# Arduino.net
KiCad netlist of a schematic drawn in EAGLE
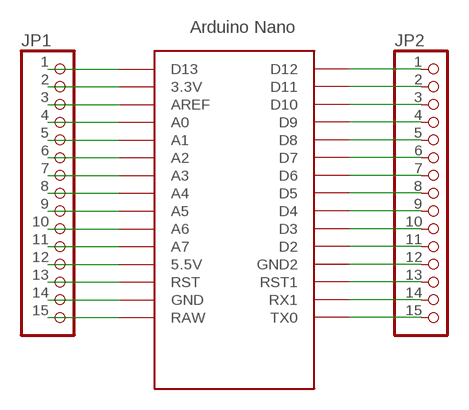
[diagram p0: schematic, sheet 1]

(export (version "E")
  (design (tool "Eeschema 10.0.6"))
  (components
    (comp (ref "JP1")
      (value "PINHD-1X15")
      (footprint "eagle-import:1X15")
      (libsource (lib "eagle-import") (part "PINHD-1X15"))
    )
    (comp (ref "JP2")
      (value "PINHD-1X15")
      (footprint "eagle-import:1X15")
      (libsource (lib "eagle-import") (part "PINHD-1X15"))
    )
    (comp (ref "U$1")
      (value "NANO")
      (footprint "eagle-import:NANO")
      (libsource (lib "eagle-import") (part "NANO"))
    )
  )
  (nets
    (net (code "1") (name "Net-(JP1-Pad1)") (class "Default")
      (node (ref "JP1") (pin "1") (pinfunction "1_1") (pintype "passive"))
      (node (ref "U$1") (pin "D13") (pinfunction "D13_D13") (pintype "bidirectional"))
    )
    (net (code "2") (name "Net-(JP1-Pad2)") (class "Default")
      (node (ref "JP1") (pin "2") (pinfunction "2_2") (pintype "passive"))
      (node (ref "U$1") (pin "3.3V") (pinfunction "3.3V_3.3V") (pintype "bidirectional"))
    )
    (net (code "3") (name "Net-(JP1-Pad3)") (class "Default")
      (node (ref "JP1") (pin "3") (pinfunction "3_3") (pintype "passive"))
      (node (ref "U$1") (pin "AREF") (pinfunction "AREF_AREF") (pintype "bidirectional"))
    )
    (net (code "4") (name "Net-(JP1-Pad4)") (class "Default")
      (node (ref "JP1") (pin "4") (pinfunction "4_4") (pintype "passive"))
      (node (ref "U$1") (pin "A0") (pinfunction "A0_A0") (pintype "bidirectional"))
    )
    (net (code "5") (name "Net-(JP1-Pad5)") (class "Default")
      (node (ref "JP1") (pin "5") (pinfunction "5_5") (pintype "passive"))
      (node (ref "U$1") (pin "A1") (pinfunction "A1_A1") (pintype "bidirectional"))
    )
    (net (code "6") (name "Net-(JP1-Pad6)") (class "Default")
      (node (ref "JP1") (pin "6") (pinfunction "6_6") (pintype "passive"))
      (node (ref "U$1") (pin "A2") (pinfunction "A2_A2") (pintype "bidirectional"))
    )
    (net (code "7") (name "Net-(JP1-Pad7)") (class "Default")
      (node (ref "JP1") (pin "7") (pinfunction "7_7") (pintype "passive"))
      (node (ref "U$1") (pin "A3") (pinfunction "A3_A3") (pintype "bidirectional"))
    )
    (net (code "8") (name "Net-(JP1-Pad8)") (class "Default")
      (node (ref "JP1") (pin "8") (pinfunction "8_8") (pintype "passive"))
      (node (ref "U$1") (pin "A4") (pinfunction "A4_A4") (pintype "bidirectional"))
    )
    (net (code "9") (name "Net-(JP1-Pad9)") (class "Default")
      (node (ref "JP1") (pin "9") (pinfunction "9_9") (pintype "passive"))
      (node (ref "U$1") (pin "A5") (pinfunction "A5_A5") (pintype "bidirectional"))
    )
    (net (code "10") (name "Net-(JP1-Pad10)") (class "Default")
      (node (ref "JP1") (pin "10") (pinfunction "10_10") (pintype "passive"))
      (node (ref "U$1") (pin "A6") (pinfunction "A6_A6") (pintype "bidirectional"))
    )
    (net (code "11") (name "Net-(JP1-Pad11)") (class "Default")
      (node (ref "JP1") (pin "11") (pinfunction "11_11") (pintype "passive"))
      (node (ref "U$1") (pin "A7") (pinfunction "A7_A7") (pintype "bidirectional"))
    )
    (net (code "12") (name "Net-(JP1-Pad13)") (class "Default")
      (node (ref "JP1") (pin "13") (pinfunction "13_13") (pintype "passive"))
      (node (ref "U$1") (pin "RST") (pinfunction "RST_RST") (pintype "bidirectional"))
    )
    (net (code "13") (name "Net-(JP1-Pad14)") (class "Default")
      (node (ref "JP1") (pin "14") (pinfunction "14_14") (pintype "passive"))
      (node (ref "U$1") (pin "GND") (pinfunction "GND_GND") (pintype "bidirectional"))
    )
    (net (code "14") (name "Net-(JP1-Pad15)") (class "Default")
      (node (ref "JP1") (pin "15") (pinfunction "15_15") (pintype "passive"))
      (node (ref "U$1") (pin "RAW") (pinfunction "RAW_RAW") (pintype "bidirectional"))
    )
    (net (code "15") (name "Net-(JP2-Pad1)") (class "Default")
      (node (ref "JP2") (pin "1") (pinfunction "1_1") (pintype "passive"))
      (node (ref "U$1") (pin "D12") (pinfunction "D12_D12") (pintype "bidirectional"))
    )
    (net (code "16") (name "Net-(JP2-Pad2)") (class "Default")
      (node (ref "JP2") (pin "2") (pinfunction "2_2") (pintype "passive"))
      (node (ref "U$1") (pin "D11") (pinfunction "D11_D11") (pintype "bidirectional"))
    )
    (net (code "17") (name "Net-(JP2-Pad3)") (class "Default")
      (node (ref "JP2") (pin "3") (pinfunction "3_3") (pintype "passive"))
      (node (ref "U$1") (pin "D10") (pinfunction "D10_D10") (pintype "bidirectional"))
    )
    (net (code "18") (name "Net-(JP2-Pad4)") (class "Default")
      (node (ref "JP2") (pin "4") (pinfunction "4_4") (pintype "passive"))
      (node (ref "U$1") (pin "D9") (pinfunction "D9_D9") (pintype "bidirectional"))
    )
    (net (code "19") (name "Net-(JP2-Pad5)") (class "Default")
      (node (ref "JP2") (pin "5") (pinfunction "5_5") (pintype "passive"))
      (node (ref "U$1") (pin "D8") (pinfunction "D8_D8") (pintype "bidirectional"))
    )
    (net (code "20") (name "Net-(JP2-Pad6)") (class "Default")
      (node (ref "JP2") (pin "6") (pinfunction "6_6") (pintype "passive"))
      (node (ref "U$1") (pin "D7") (pinfunction "D7_D7") (pintype "bidirectional"))
    )
    (net (code "21") (name "Net-(JP2-Pad7)") (class "Default")
      (node (ref "JP2") (pin "7") (pinfunction "7_7") (pintype "passive"))
      (node (ref "U$1") (pin "D6") (pinfunction "D6_D6") (pintype "bidirectional"))
    )
    (net (code "22") (name "Net-(JP2-Pad8)") (class "Default")
      (node (ref "JP2") (pin "8") (pinfunction "8_8") (pintype "passive"))
      (node (ref "U$1") (pin "D5") (pinfunction "D5_D5") (pintype "bidirectional"))
    )
    (net (code "23") (name "Net-(JP2-Pad9)") (class "Default")
      (node (ref "JP2") (pin "9") (pinfunction "9_9") (pintype "passive"))
      (node (ref "U$1") (pin "D4") (pinfunction "D4_D4") (pintype "bidirectional"))
    )
    (net (code "24") (name "Net-(JP2-Pad10)") (class "Default")
      (node (ref "JP2") (pin "10") (pinfunction "10_10") (pintype "passive"))
      (node (ref "U$1") (pin "D3") (pinfunction "D3_D3") (pintype "bidirectional"))
    )
    (net (code "25") (name "Net-(JP2-Pad11)") (class "Default")
      (node (ref "JP2") (pin "11") (pinfunction "11_11") (pintype "passive"))
      (node (ref "U$1") (pin "D2") (pinfunction "D2_D2") (pintype "bidirectional"))
    )
    (net (code "26") (name "Net-(JP2-Pad13)") (class "Default")
      (node (ref "JP2") (pin "13") (pinfunction "13_13") (pintype "passive"))
      (node (ref "U$1") (pin "RST1") (pinfunction "RST1_RST1") (pintype "bidirectional"))
    )
    (net (code "27") (name "Net-(JP2-Pad14)") (class "Default")
      (node (ref "JP2") (pin "14") (pinfunction "14_14") (pintype "passive"))
      (node (ref "U$1") (pin "RX1") (pinfunction "RX1_RX1") (pintype "bidirectional"))
    )
    (net (code "28") (name "Net-(JP2-Pad15)") (class "Default")
      (node (ref "JP2") (pin "15") (pinfunction "15_15") (pintype "passive"))
      (node (ref "U$1") (pin "TX0") (pinfunction "TX0_TX0") (pintype "bidirectional"))
    )
    (net (code "29") (name "Net-(U$1-5.5V)") (class "Default")
      (node (ref "JP1") (pin "12") (pinfunction "12_12") (pintype "passive"))
      (node (ref "U$1") (pin "5V") (pinfunction "5.5V_5V") (pintype "bidirectional"))
    )
    (net (code "30") (name "Net-(U$1-GND2)") (class "Default")
      (node (ref "JP2") (pin "12") (pinfunction "12_12") (pintype "passive"))
      (node (ref "U$1") (pin "GND1") (pinfunction "GND2_GND1") (pintype "bidirectional"))
    )
    (net (code "31") (name "unconnected-(U$1-PadICSP1)") (class "Default")
      (node (ref "U$1") (pin "ICSP1") (pinfunction "ICSP1_ICSP1") (pintype "bidirectional"))
    )
    (net (code "32") (name "unconnected-(U$1-PadICSP2)") (class "Default")
      (node (ref "U$1") (pin "ICSP2") (pinfunction "ICSP2_ICSP2") (pintype "bidirectional"))
    )
    (net (code "33") (name "unconnected-(U$1-PadICSP3)") (class "Default")
      (node (ref "U$1") (pin "ICSP3") (pinfunction "ICSP3_ICSP3") (pintype "bidirectional"))
    )
    (net (code "34") (name "unconnected-(U$1-PadICSP4)") (class "Default")
      (node (ref "U$1") (pin "ICSP4") (pinfunction "ICSP4_ICSP4") (pintype "bidirectional"))
    )
    (net (code "35") (name "unconnected-(U$1-PadICSP5)") (class "Default")
      (node (ref "U$1") (pin "ICSP5") (pinfunction "ICSP5_ICSP5") (pintype "bidirectional"))
    )
    (net (code "36") (name "unconnected-(U$1-PadICSP6)") (class "Default")
      (node (ref "U$1") (pin "ICSP6") (pinfunction "ICSP6_ICSP6") (pintype "bidirectional"))
    )
  )
)
